# 3_STM32F334R8T6Board_Interfaces.net
KiCad netlist of a schematic drawn in Altium Designer
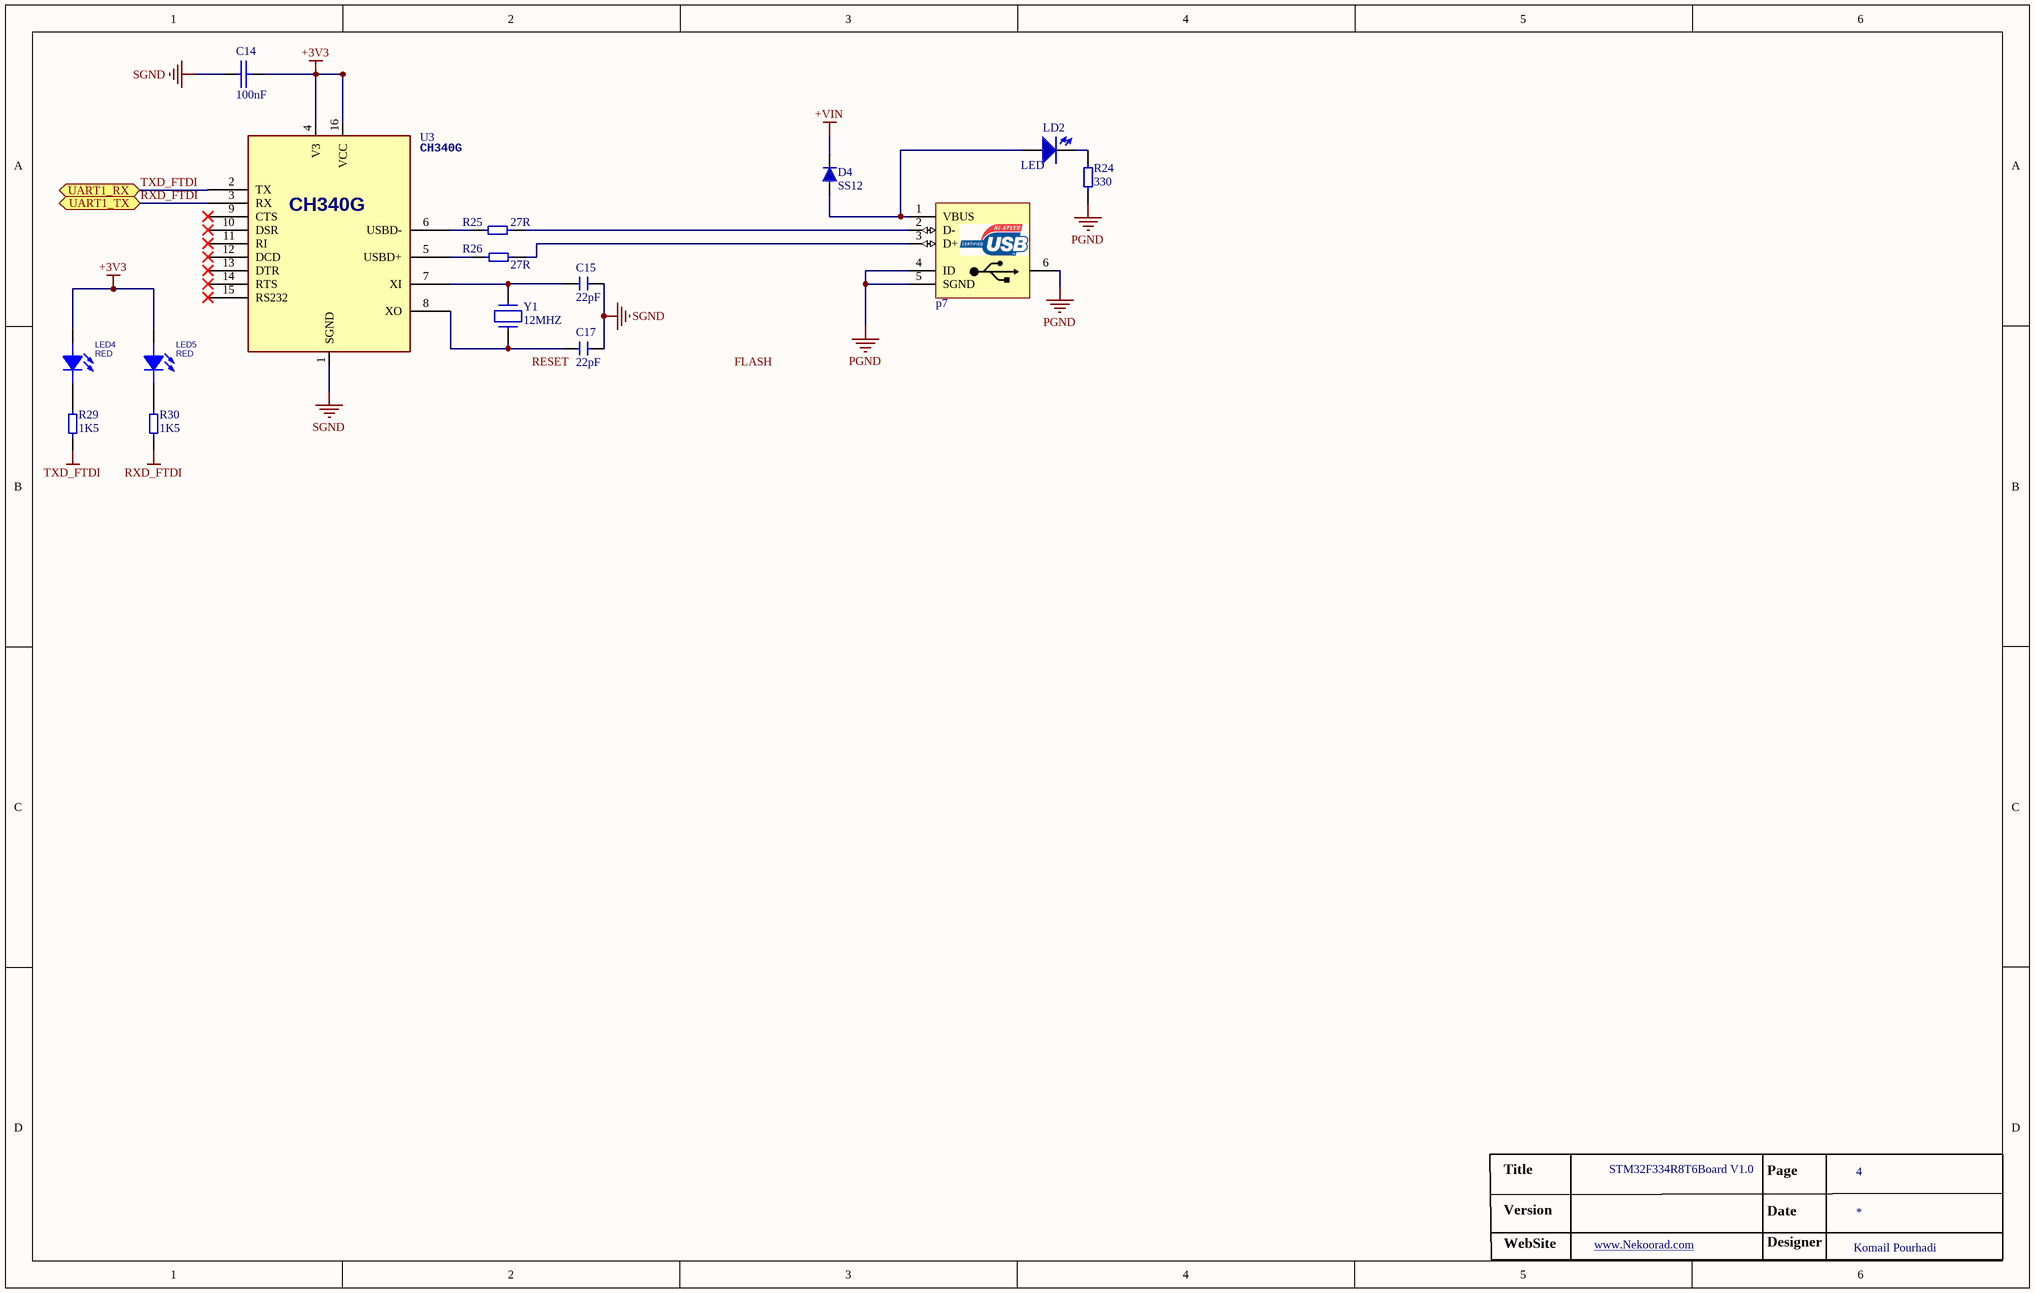
[diagram p0: [3]STM32F334R8T6Board_Interfaces.SchDoc]

(export (version "E")
  (design (tool "Eeschema 10.0.6"))
  (components
    (comp (ref "C14")
      (value "100nF")
      (footprint "SMD_CAP_1206")
      (description "Bipolar Capacitor")
      (fields
        (field (name "VOLTAGE") "100V")
        (field (name "Comment") "Comment")
        (field (name "DESIGNER") "Saeid Jorablo")
      )
      (libsource (lib "DotexGroup_LIB") (part "Cap-Bipolar"))
    )
    (comp (ref "C15")
      (value "Comment")
      (footprint "SMD_CAP_1206")
      (fields (field (name "ALTIUM_UNNAMED_1") "22pF"))
      (libsource (lib "DotexGroup_LIB") (part "Capacitor SMD"))
    )
    (comp (ref "C17")
      (value "Comment")
      (footprint "SMD_CAP_1206")
      (fields (field (name "ALTIUM_UNNAMED_1") "22pF"))
      (libsource (lib "DotexGroup_LIB") (part "Capacitor SMD"))
    )
    (comp (ref "D4")
      (value "SS12")
      (footprint "Diode SMA-M")
      (libsource (lib "DotexGroup_LIB") (part "1N4001"))
    )
    (comp (ref "LD2")
      (value "LED")
      (footprint "LED_0805 Y")
      (libsource (lib "DotexGroup_LIB") (part "LED SMD"))
    )
    (comp (ref "LED4")
      (value "RED")
      (footprint "LED SMD 1206")
      (description "Light Emitting Diode")
      (fields (field (name "DESIGNER") "Abbas Basereh"))
      (libsource (lib "Schematic") (part "LED 5MM"))
    )
    (comp (ref "LED5")
      (value "RED")
      (footprint "LED SMD 1206")
      (description "Light Emitting Diode")
      (fields (field (name "DESIGNER") "Abbas Basereh"))
      (libsource (lib "Schematic") (part "LED 5MM"))
    )
    (comp (ref "p7")
      (value "USB Connector")
      (footprint "USB Micro")
      (description "USB MICRO-B Type Connector")
      (fields (field (name "DESIGNER") "ABBAS BASEREH") (field (name "PUBLISHER") "ABBAS BASEREH"))
      (libsource (lib "DotexGroup_LIB") (part "USB AB MICRO CONNECTOR"))
    )
    (comp (ref "R24")
      (value "Comment")
      (footprint "RES_1206")
      (fields (field (name "ALTIUM_UNNAMED_1") "330"))
      (libsource (lib "DotexGroup_LIB") (part "Resistor SMD"))
    )
    (comp (ref "R25")
      (value "Comment")
      (footprint "RES_1206")
      (fields (field (name "ALTIUM_UNNAMED_1") "27R"))
      (libsource (lib "DotexGroup_LIB") (part "Resistor SMD"))
    )
    (comp (ref "R26")
      (value "Comment")
      (footprint "RES_1206")
      (fields (field (name "ALTIUM_UNNAMED_1") "27R"))
      (libsource (lib "DotexGroup_LIB") (part "Resistor SMD"))
    )
    (comp (ref "R29")
      (value "RESISTOR")
      (footprint "RES_1206")
      (fields (field (name "ALTIUM_UNNAMED_1") "1K5"))
      (libsource (lib "ZetaBoard_Lib") (part "Resistor SMD"))
    )
    (comp (ref "R30")
      (value "RESISTOR")
      (footprint "RES_1206")
      (fields (field (name "ALTIUM_UNNAMED_1") "1K5"))
      (libsource (lib "ZetaBoard_Lib") (part "Resistor SMD"))
    )
    (comp (ref "U3")
      (value "CH340G")
      (footprint "Header smd 2*8")
      (description "USB-UART")
      (libsource (lib "DotexGroup_LIB") (part "CH340G_SOP16"))
    )
    (comp (ref "Y1")
      (value "12MHZ")
      (footprint "Crystal SMD")
      (libsource (lib "DotexGroup_LIB") (part "Xtal"))
    )
  )
  (nets
    (net (code "1") (name "+3V3") (class "Default")
      (node (ref "C14") (pin "2") (pinfunction "-_2") (pintype "passive"))
      (node (ref "LED4") (pin "1") (pinfunction "ANODE_1") (pintype "passive"))
      (node (ref "LED5") (pin "1") (pinfunction "ANODE_1") (pintype "passive"))
      (node (ref "U3") (pin "16") (pinfunction "VCC_16") (pintype "passive"))
      (node (ref "U3") (pin "4") (pinfunction "V3_4") (pintype "passive"))
    )
    (net (code "2") (name "+VIN") (class "Default")
      (node (ref "D4") (pin "2") (pinfunction "K_2") (pintype "passive"))
    )
    (net (code "5") (name "Net-(D4-A)") (class "Default")
      (node (ref "D4") (pin "1") (pinfunction "A_1") (pintype "passive"))
      (node (ref "LD2") (pin "1") (pinfunction "A_1") (pintype "passive"))
      (node (ref "p7") (pin "1") (pinfunction "VBUS_1") (pintype "power_in"))
    )
    (net (code "6") (name "Net-(LD2-K)") (class "Default")
      (node (ref "LD2") (pin "2") (pinfunction "K_2") (pintype "passive"))
      (node (ref "R24") (pin "1") (pintype "passive"))
    )
    (net (code "7") (name "Net-(LED4-CATHODE)") (class "Default")
      (node (ref "LED4") (pin "2") (pinfunction "CATHODE_2") (pintype "passive"))
      (node (ref "R29") (pin "2") (pintype "passive"))
    )
    (net (code "8") (name "Net-(LED5-CATHODE)") (class "Default")
      (node (ref "LED5") (pin "2") (pinfunction "CATHODE_2") (pintype "passive"))
      (node (ref "R30") (pin "2") (pintype "passive"))
    )
    (net (code "9") (name "Net-(U3-USBD+)") (class "Default")
      (node (ref "R26") (pin "1") (pintype "passive"))
      (node (ref "U3") (pin "5") (pinfunction "USBD+_5") (pintype "passive"))
    )
    (net (code "10") (name "Net-(U3-USBD-)") (class "Default")
      (node (ref "R25") (pin "1") (pintype "passive"))
      (node (ref "U3") (pin "6") (pinfunction "USBD-_6") (pintype "passive"))
    )
    (net (code "11") (name "Net-(U3-XI)") (class "Default")
      (node (ref "C15") (pin "2") (pintype "passive"))
      (node (ref "U3") (pin "7") (pinfunction "XI_7") (pintype "passive"))
      (node (ref "Y1") (pin "2") (pintype "passive"))
    )
    (net (code "12") (name "Net-(U3-XO)") (class "Default")
      (node (ref "C17") (pin "1") (pintype "passive"))
      (node (ref "U3") (pin "8") (pinfunction "XO_8") (pintype "passive"))
      (node (ref "Y1") (pin "1") (pintype "passive"))
    )
    (net (code "13") (name "Net-(p7-D+)") (class "Default")
      (node (ref "R26") (pin "2") (pintype "passive"))
      (node (ref "p7") (pin "3") (pinfunction "D+_3") (pintype "bidirectional"))
    )
    (net (code "14") (name "Net-(p7-D-)") (class "Default")
      (node (ref "R25") (pin "2") (pintype "passive"))
      (node (ref "p7") (pin "2") (pinfunction "D-_2") (pintype "bidirectional"))
    )
    (net (code "15") (name "PGND") (class "Default")
      (node (ref "R24") (pin "2") (pintype "passive"))
      (node (ref "p7") (pin "4") (pinfunction "ID_4") (pintype "power_in"))
      (node (ref "p7") (pin "5") (pinfunction "SGND_5") (pintype "power_in"))
      (node (ref "p7") (pin "6") (pinfunction "MH_6") (pintype "power_in"))
    )
    (net (code "16") (name "RXD_FTDI") (class "Default")
      (node (ref "R30") (pin "1") (pintype "passive"))
      (node (ref "U3") (pin "3") (pinfunction "RX_3") (pintype "passive"))
    )
    (net (code "17") (name "SGND") (class "Default")
      (node (ref "C14") (pin "1") (pinfunction "+_1") (pintype "passive"))
      (node (ref "C15") (pin "1") (pintype "passive"))
      (node (ref "C17") (pin "2") (pintype "passive"))
      (node (ref "U3") (pin "1") (pinfunction "SGND_1") (pintype "passive"))
    )
    (net (code "18") (name "TXD_FTDI") (class "Default")
      (node (ref "R29") (pin "1") (pintype "passive"))
      (node (ref "U3") (pin "2") (pinfunction "TX_2") (pintype "passive"))
    )
    (net (code "19") (name "unconnected-(U3-CTS-Pad9)") (class "Default")
      (node (ref "U3") (pin "9") (pinfunction "CTS_9") (pintype "passive+no_connect"))
    )
    (net (code "20") (name "unconnected-(U3-DCD-Pad12)") (class "Default")
      (node (ref "U3") (pin "12") (pinfunction "DCD_12") (pintype "passive+no_connect"))
    )
    (net (code "21") (name "unconnected-(U3-DSR-Pad10)") (class "Default")
      (node (ref "U3") (pin "10") (pinfunction "DSR_10") (pintype "passive+no_connect"))
    )
    (net (code "22") (name "unconnected-(U3-DTR-Pad13)") (class "Default")
      (node (ref "U3") (pin "13") (pinfunction "DTR_13") (pintype "passive+no_connect"))
    )
    (net (code "23") (name "unconnected-(U3-RI-Pad11)") (class "Default")
      (node (ref "U3") (pin "11") (pinfunction "RI_11") (pintype "passive+no_connect"))
    )
    (net (code "24") (name "unconnected-(U3-RS232-Pad15)") (class "Default")
      (node (ref "U3") (pin "15") (pinfunction "RS232_15") (pintype "passive+no_connect"))
    )
    (net (code "25") (name "unconnected-(U3-RTS-Pad14)") (class "Default")
      (node (ref "U3") (pin "14") (pinfunction "RTS_14") (pintype "passive+no_connect"))
    )
  )
)
